# ELEKID_POWER.net
KiCad netlist of a schematic drawn in Altium Designer
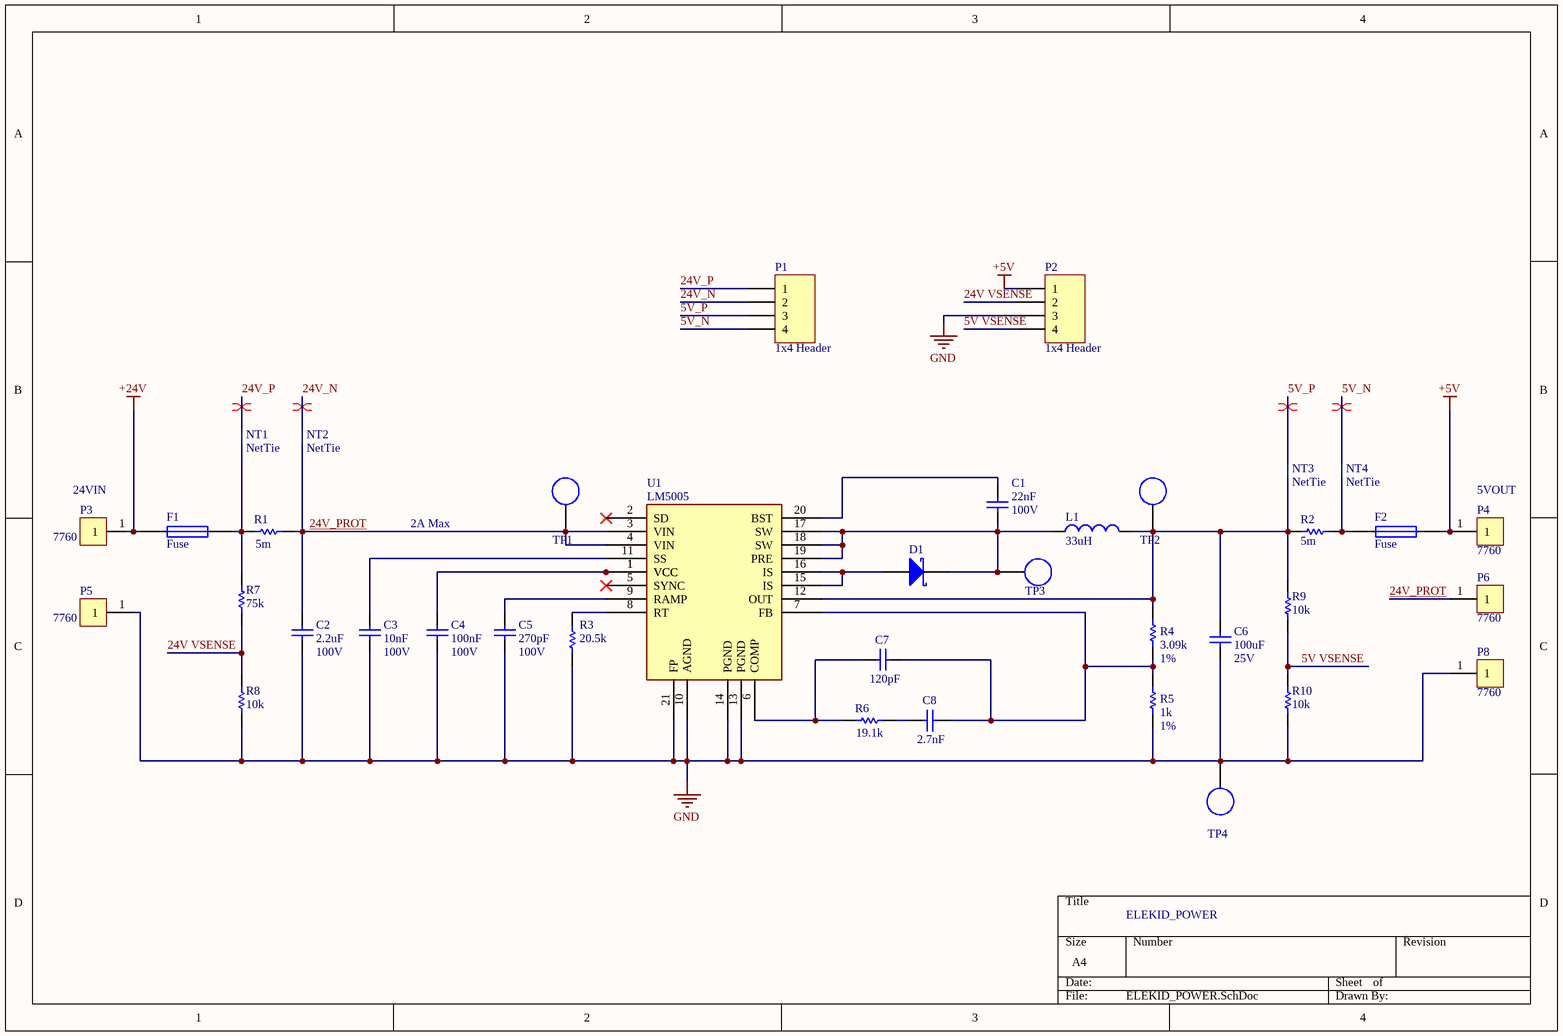
[diagram p0: ELEKID_POWER.SchDoc]

(export (version "E")
  (design (tool "Eeschema 10.0.6"))
  (components
    (comp (ref "C1")
      (value "22nF")
      (footprint "0805 - Capacitor")
      (description "Nonpolarized Capacitor")
      (libsource (lib "General") (part "Capacitor - Nonpolarized"))
    )
    (comp (ref "C2")
      (value "2.2uF")
      (footprint "0805 - Capacitor")
      (description "Nonpolarized Capacitor")
      (libsource (lib "General") (part "Capacitor - Nonpolarized"))
    )
    (comp (ref "C3")
      (value "10nF")
      (footprint "0805 - Capacitor")
      (description "Nonpolarized Capacitor")
      (libsource (lib "General") (part "Capacitor - Nonpolarized"))
    )
    (comp (ref "C4")
      (value "100nF")
      (footprint "0805 - Capacitor")
      (description "Nonpolarized Capacitor")
      (libsource (lib "General") (part "Capacitor - Nonpolarized"))
    )
    (comp (ref "C5")
      (value "270pF")
      (footprint "0805 - Capacitor")
      (description "Nonpolarized Capacitor")
      (libsource (lib "General") (part "Capacitor - Nonpolarized"))
    )
    (comp (ref "C6")
      (value "100uF")
      (footprint "1206 - Capacitor")
      (description "Nonpolarized Capacitor")
      (fields (field (name "Comment") "Capacitor - Nonpolarized"))
      (libsource (lib "General") (part "Capacitor - Nonpolarized"))
    )
    (comp (ref "C7")
      (value "120pF")
      (footprint "0805 - Capacitor")
      (description "Nonpolarized Capacitor")
      (libsource (lib "General") (part "Capacitor - Nonpolarized"))
    )
    (comp (ref "C8")
      (value "2.7nF")
      (footprint "0805 - Capacitor")
      (description "Nonpolarized Capacitor")
      (libsource (lib "General") (part "Capacitor - Nonpolarized"))
    )
    (comp (ref "D1")
      (value "Diode - Schottky")
      (footprint "SMA - DIODE")
      (description "Schottky Rectifier")
      (libsource (lib "General") (part "Diode - Schottky"))
    )
    (comp (ref "F1") (value "Fuse") (footprint "3557-2") (libsource (lib "General") (part "Fuse")))
    (comp (ref "F2") (value "Fuse") (footprint "3557-2") (libsource (lib "General") (part "Fuse")))
    (comp (ref "L1")
      (value "33uH")
      (footprint "MSS1210 - INDUCTOR")
      (description "Inductor")
      (libsource (lib "General") (part "Inductor"))
    )
    (comp (ref "NT1") (value "NetTie") (footprint "Net Tie") (libsource (lib "General") (part "Net Tie")))
    (comp (ref "NT2") (value "NetTie") (footprint "Net Tie") (libsource (lib "General") (part "Net Tie")))
    (comp (ref "NT3") (value "NetTie") (footprint "Net Tie") (libsource (lib "General") (part "Net Tie")))
    (comp (ref "NT4") (value "NetTie") (footprint "Net Tie") (libsource (lib "General") (part "Net Tie")))
    (comp (ref "P1")
      (value "1x4 Header")
      (footprint "B4B-XH")
      (description "1x4 Pin Header")
      (libsource (lib "GeneralConnectors") (part "1x4 Header"))
    )
    (comp (ref "P2")
      (value "1x4 Header")
      (footprint "B4B-XH")
      (description "1x4 Pin Header")
      (libsource (lib "GeneralConnectors") (part "1x4 Header"))
    )
    (comp (ref "P3") (value "7760") (footprint "7760") (libsource (lib "") (part "7760_1")))
    (comp (ref "P4") (value "7760") (footprint "7760") (libsource (lib "GeneralConnectors") (part "7760")))
    (comp (ref "P5") (value "7760") (footprint "7760") (libsource (lib "") (part "7760_1")))
    (comp (ref "P6") (value "7760") (footprint "7760") (libsource (lib "GeneralConnectors") (part "7760")))
    (comp (ref "P8") (value "7760") (footprint "7760") (libsource (lib "GeneralConnectors") (part "7760")))
    (comp (ref "R1")
      (value "5m")
      (footprint "0603 - Resistor")
      (description "Resistor")
      (libsource (lib "General") (part "Resistor"))
    )
    (comp (ref "R2")
      (value "5m")
      (footprint "0603 - Resistor")
      (description "Resistor")
      (libsource (lib "General") (part "Resistor"))
    )
    (comp (ref "R3")
      (value "20.5k")
      (footprint "0603 - Resistor")
      (description "Resistor")
      (libsource (lib "General") (part "Resistor"))
    )
    (comp (ref "R4")
      (value "3.09k")
      (footprint "0603 - Resistor")
      (description "Resistor")
      (libsource (lib "General") (part "Resistor"))
    )
    (comp (ref "R5")
      (value "1k")
      (footprint "0805 - Resistor")
      (description "Resistor")
      (libsource (lib "General") (part "Resistor"))
    )
    (comp (ref "R6")
      (value "19.1k")
      (footprint "0603 - Resistor")
      (description "Resistor")
      (libsource (lib "General") (part "Resistor"))
    )
    (comp (ref "R7")
      (value "75k")
      (footprint "0603 - Resistor")
      (description "Resistor")
      (libsource (lib "General") (part "Resistor"))
    )
    (comp (ref "R8")
      (value "10k")
      (footprint "0603 - Resistor")
      (description "Resistor")
      (libsource (lib "General") (part "Resistor"))
    )
    (comp (ref "R9")
      (value "10k")
      (footprint "0603 - Resistor")
      (description "Resistor")
      (libsource (lib "General") (part "Resistor"))
    )
    (comp (ref "R10")
      (value "10k")
      (footprint "0603 - Resistor")
      (description "Resistor")
      (libsource (lib "General") (part "Resistor"))
    )
    (comp (ref "TP1")
      (value "Test Point")
      (footprint "Test Point")
      (libsource (lib "General") (part "Test Point"))
    )
    (comp (ref "TP2")
      (value "Test Point")
      (footprint "Test Point")
      (libsource (lib "General") (part "Test Point"))
    )
    (comp (ref "TP3")
      (value "Test Point")
      (footprint "Test Point")
      (libsource (lib "General") (part "Test Point"))
    )
    (comp (ref "TP4")
      (value "Test Point")
      (footprint "Test Point")
      (libsource (lib "General") (part "Test Point"))
    )
    (comp (ref "U1")
      (value "LM5005")
      (footprint "LM5005")
      (description "7V to 75V 2.5A, Buck Converter")
      (fields
        (field (name "MANUFACTURER") "Texas Instruments")
        (field (name "MANUFACTURER PART NUMBER") "LM5005MHX/NOPB")
      )
      (libsource (lib "GeneralComponents") (part "LM5005"))
    )
  )
  (nets
    (net (code "1") (name "+5V") (class "Default")
      (node (ref "F2") (pin "1") (pinfunction "1_1") (pintype "passive"))
      (node (ref "P2") (pin "1") (pinfunction "1_1") (pintype "passive"))
      (node (ref "P4") (pin "1") (pinfunction "1_1") (pintype "passive"))
    )
    (net (code "2") (name "+24V") (class "Default")
      (node (ref "F1") (pin "2") (pinfunction "2_2") (pintype "passive"))
      (node (ref "P3") (pin "1") (pinfunction "1_1") (pintype "passive"))
    )
    (net (code "3") (name "/5V VSENSE") (class "Default")
      (node (ref "P2") (pin "4") (pinfunction "4_4") (pintype "passive"))
      (node (ref "R10") (pin "2") (pinfunction "2_2") (pintype "passive"))
      (node (ref "R9") (pin "1") (pinfunction "1_1") (pintype "passive"))
    )
    (net (code "4") (name "/5V_N") (class "Default")
      (node (ref "NT4") (pin "2") (pinfunction "2_2") (pintype "passive"))
      (node (ref "P1") (pin "4") (pinfunction "4_4") (pintype "passive"))
    )
    (net (code "5") (name "/5V_P") (class "Default")
      (node (ref "NT3") (pin "2") (pinfunction "2_2") (pintype "passive"))
      (node (ref "P1") (pin "3") (pinfunction "3_3") (pintype "passive"))
    )
    (net (code "6") (name "/24V VSENSE") (class "Default")
      (node (ref "P2") (pin "2") (pinfunction "2_2") (pintype "passive"))
      (node (ref "R7") (pin "1") (pinfunction "1_1") (pintype "passive"))
      (node (ref "R8") (pin "1") (pinfunction "1_1") (pintype "passive"))
    )
    (net (code "7") (name "/24V_N") (class "Default")
      (node (ref "NT2") (pin "2") (pinfunction "2_2") (pintype "passive"))
      (node (ref "P1") (pin "2") (pinfunction "2_2") (pintype "passive"))
    )
    (net (code "8") (name "/24V_P") (class "Default")
      (node (ref "NT1") (pin "2") (pinfunction "2_2") (pintype "passive"))
      (node (ref "P1") (pin "1") (pinfunction "1_1") (pintype "passive"))
    )
    (net (code "9") (name "/24V_PROT") (class "Default")
      (node (ref "C2") (pin "2") (pinfunction "2_2") (pintype "passive"))
      (node (ref "NT2") (pin "1") (pinfunction "1_1") (pintype "passive"))
      (node (ref "P6") (pin "1") (pinfunction "1_1") (pintype "passive"))
      (node (ref "R1") (pin "1") (pinfunction "1_1") (pintype "passive"))
      (node (ref "TP1") (pin "0") (pinfunction "0_0") (pintype "passive"))
      (node (ref "U1") (pin "3") (pinfunction "VIN_3") (pintype "passive"))
      (node (ref "U1") (pin "4") (pinfunction "VIN_4") (pintype "passive"))
    )
    (net (code "11") (name "GND") (class "Default")
      (node (ref "C2") (pin "1") (pinfunction "1_1") (pintype "passive"))
      (node (ref "C3") (pin "1") (pinfunction "1_1") (pintype "passive"))
      (node (ref "C4") (pin "1") (pinfunction "1_1") (pintype "passive"))
      (node (ref "C5") (pin "1") (pinfunction "1_1") (pintype "passive"))
      (node (ref "C6") (pin "2") (pinfunction "2_2") (pintype "passive"))
      (node (ref "P2") (pin "3") (pinfunction "3_3") (pintype "passive"))
      (node (ref "P5") (pin "1") (pinfunction "1_1") (pintype "passive"))
      (node (ref "P8") (pin "1") (pinfunction "1_1") (pintype "passive"))
      (node (ref "R10") (pin "1") (pinfunction "1_1") (pintype "passive"))
      (node (ref "R3") (pin "1") (pinfunction "1_1") (pintype "passive"))
      (node (ref "R5") (pin "1") (pinfunction "1_1") (pintype "passive"))
      (node (ref "R8") (pin "2") (pinfunction "2_2") (pintype "passive"))
      (node (ref "TP4") (pin "0") (pinfunction "0_0") (pintype "passive"))
      (node (ref "U1") (pin "10") (pinfunction "AGND_10") (pintype "passive"))
      (node (ref "U1") (pin "13") (pinfunction "PGND_13") (pintype "passive"))
      (node (ref "U1") (pin "14") (pinfunction "PGND_14") (pintype "passive"))
      (node (ref "U1") (pin "21") (pinfunction "FP_21") (pintype "passive"))
    )
    (net (code "12") (name "Net-(C8-Pad2)") (class "Default")
      (node (ref "C8") (pin "2") (pinfunction "2_2") (pintype "passive"))
      (node (ref "R6") (pin "1") (pinfunction "1_1") (pintype "passive"))
    )
    (net (code "13") (name "Net-(D1-A)") (class "Default")
      (node (ref "D1") (pin "1") (pinfunction "A_1") (pintype "passive"))
      (node (ref "U1") (pin "15") (pinfunction "IS_15") (pintype "passive"))
      (node (ref "U1") (pin "16") (pinfunction "IS_16") (pintype "passive"))
    )
    (net (code "14") (name "Net-(D1-K)") (class "Default")
      (node (ref "C1") (pin "1") (pinfunction "1_1") (pintype "passive"))
      (node (ref "D1") (pin "2") (pinfunction "K_2") (pintype "passive"))
      (node (ref "L1") (pin "1") (pinfunction "1_1") (pintype "passive"))
      (node (ref "TP3") (pin "0") (pinfunction "0_0") (pintype "passive"))
      (node (ref "U1") (pin "17") (pinfunction "SW_17") (pintype "passive"))
      (node (ref "U1") (pin "18") (pinfunction "SW_18") (pintype "passive"))
      (node (ref "U1") (pin "19") (pinfunction "PRE_19") (pintype "passive"))
    )
    (net (code "15") (name "Net-(F1-Pad1)") (class "Default")
      (node (ref "F1") (pin "1") (pinfunction "1_1") (pintype "passive"))
      (node (ref "NT1") (pin "1") (pinfunction "1_1") (pintype "passive"))
      (node (ref "R1") (pin "2") (pinfunction "2_2") (pintype "passive"))
      (node (ref "R7") (pin "2") (pinfunction "2_2") (pintype "passive"))
    )
    (net (code "16") (name "Net-(F2-Pad2)") (class "Default")
      (node (ref "F2") (pin "2") (pinfunction "2_2") (pintype "passive"))
      (node (ref "NT4") (pin "1") (pinfunction "1_1") (pintype "passive"))
      (node (ref "R2") (pin "2") (pinfunction "2_2") (pintype "passive"))
    )
    (net (code "17") (name "Net-(U1-BST)") (class "Default")
      (node (ref "C1") (pin "2") (pinfunction "2_2") (pintype "passive"))
      (node (ref "U1") (pin "20") (pinfunction "BST_20") (pintype "passive"))
    )
    (net (code "18") (name "Net-(U1-COMP)") (class "Default")
      (node (ref "C7") (pin "2") (pinfunction "2_2") (pintype "passive"))
      (node (ref "R6") (pin "2") (pinfunction "2_2") (pintype "passive"))
      (node (ref "U1") (pin "6") (pinfunction "COMP_6") (pintype "passive"))
    )
    (net (code "19") (name "Net-(U1-FB)") (class "Default")
      (node (ref "C7") (pin "1") (pinfunction "1_1") (pintype "passive"))
      (node (ref "C8") (pin "1") (pinfunction "1_1") (pintype "passive"))
      (node (ref "R4") (pin "1") (pinfunction "1_1") (pintype "passive"))
      (node (ref "R5") (pin "2") (pinfunction "2_2") (pintype "passive"))
      (node (ref "U1") (pin "7") (pinfunction "FB_7") (pintype "passive"))
    )
    (net (code "20") (name "Net-(U1-OUT)") (class "Default")
      (node (ref "C6") (pin "1") (pinfunction "1_1") (pintype "passive"))
      (node (ref "L1") (pin "2") (pinfunction "2_2") (pintype "passive"))
      (node (ref "NT3") (pin "1") (pinfunction "1_1") (pintype "passive"))
      (node (ref "R2") (pin "1") (pinfunction "1_1") (pintype "passive"))
      (node (ref "R4") (pin "2") (pinfunction "2_2") (pintype "passive"))
      (node (ref "R9") (pin "2") (pinfunction "2_2") (pintype "passive"))
      (node (ref "TP2") (pin "0") (pinfunction "0_0") (pintype "passive"))
      (node (ref "U1") (pin "12") (pinfunction "OUT_12") (pintype "passive"))
    )
    (net (code "21") (name "Net-(U1-RAMP)") (class "Default")
      (node (ref "C5") (pin "2") (pinfunction "2_2") (pintype "passive"))
      (node (ref "U1") (pin "9") (pinfunction "RAMP_9") (pintype "passive"))
    )
    (net (code "22") (name "Net-(U1-RT)") (class "Default")
      (node (ref "R3") (pin "2") (pinfunction "2_2") (pintype "passive"))
      (node (ref "U1") (pin "8") (pinfunction "RT_8") (pintype "passive"))
    )
    (net (code "23") (name "Net-(U1-SS)") (class "Default")
      (node (ref "C3") (pin "2") (pinfunction "2_2") (pintype "passive"))
      (node (ref "U1") (pin "11") (pinfunction "SS_11") (pintype "passive"))
    )
    (net (code "24") (name "Net-(U1-VCC)") (class "Default")
      (node (ref "C4") (pin "2") (pinfunction "2_2") (pintype "passive"))
      (node (ref "U1") (pin "1") (pinfunction "VCC_1") (pintype "passive"))
    )
    (net (code "25") (name "unconnected-(U1-SD-Pad2)") (class "Default")
      (node (ref "U1") (pin "2") (pinfunction "SD_2") (pintype "passive+no_connect"))
    )
    (net (code "26") (name "unconnected-(U1-SYNC-Pad5)") (class "Default")
      (node (ref "U1") (pin "5") (pinfunction "SYNC_5") (pintype "passive+no_connect"))
    )
  )
)
